# BBoard-JX1.net
KiCad netlist of a schematic drawn in Altium Designer
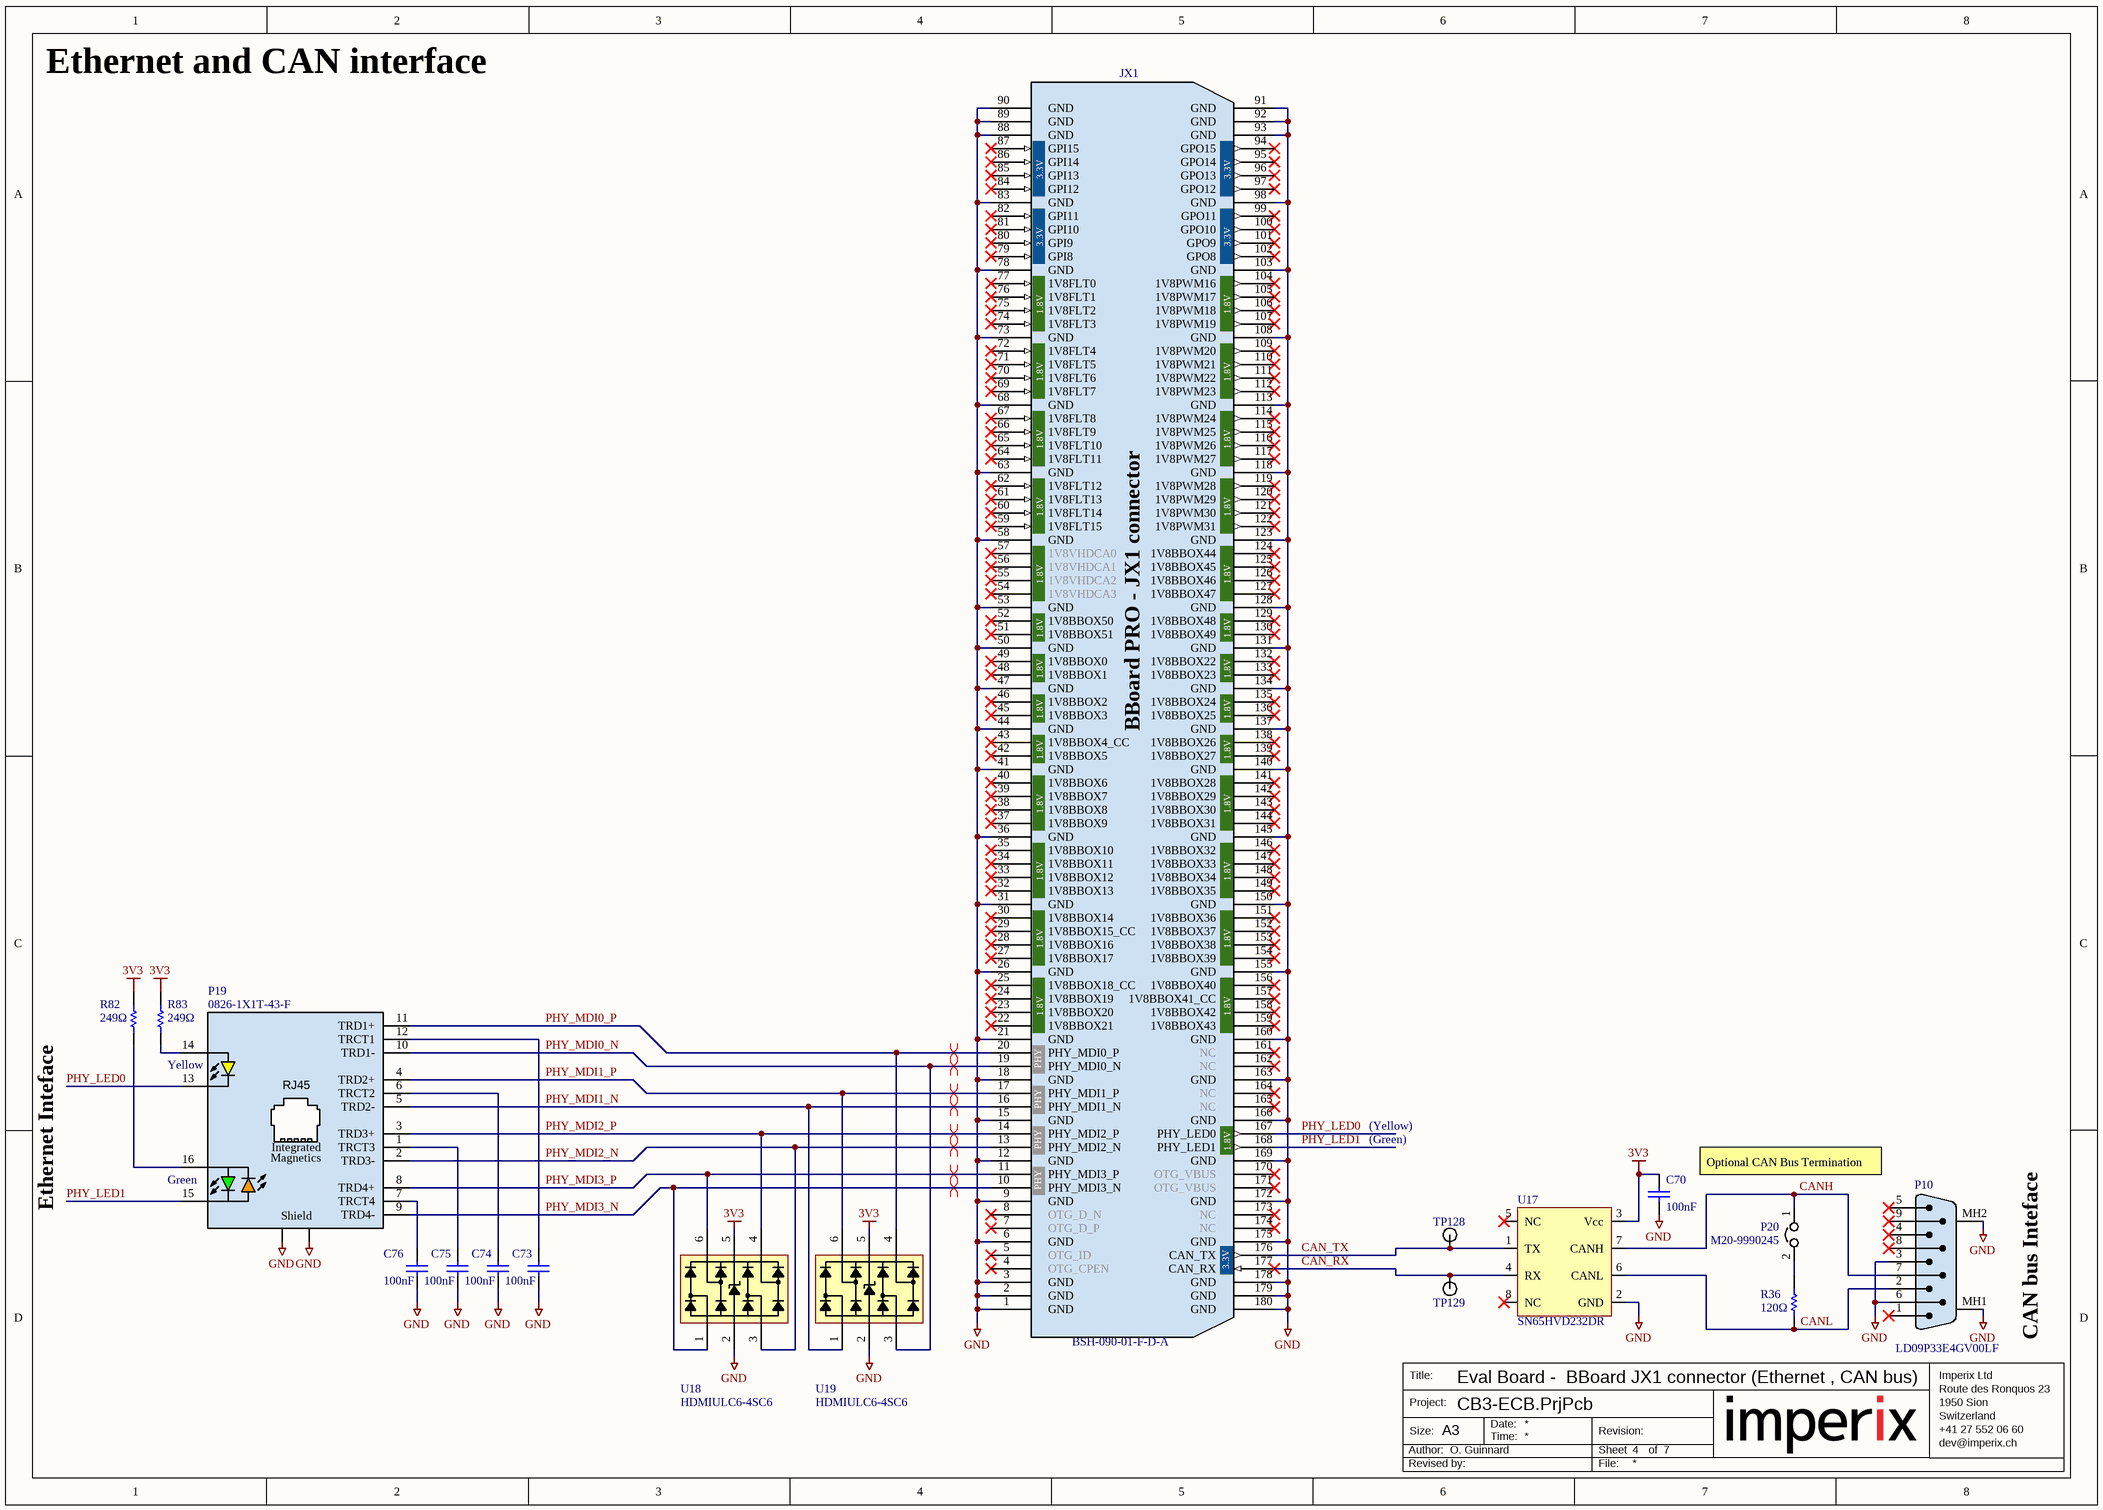
[diagram p0: BBoard-JX1.SchDoc]

(export (version "E")
  (design (tool "Eeschema 10.0.6"))
  (components
    (comp (ref "C70")
      (value "100nF")
      (footprint "CAPC1005L(0402)")
      (description "CAP CER 100NF 25V X7R 0402 10% (Generic Imperix Component)")
      (fields (field (name "TOLERANCE") "10%") (field (name "Comment") "CAP-100NF-25V-X7R-0402-10%"))
      (libsource (lib "CB3-ECB") (part "Capacitor non-polarized"))
    )
    (comp (ref "C73")
      (value "100nF")
      (footprint "CAPC1005L(0402)")
      (description "CAP CER 100NF 25V X7R 0402 10% (Generic Imperix Component)")
      (fields (field (name "TOLERANCE") "10%") (field (name "Comment") "CAP-100NF-25V-X7R-0402-10%"))
      (libsource (lib "CB3-ECB") (part "Capacitor non-polarized"))
    )
    (comp (ref "C74")
      (value "100nF")
      (footprint "CAPC1005L(0402)")
      (description "CAP CER 100NF 25V X7R 0402 10% (Generic Imperix Component)")
      (fields (field (name "TOLERANCE") "10%") (field (name "Comment") "CAP-100NF-25V-X7R-0402-10%"))
      (libsource (lib "CB3-ECB") (part "Capacitor non-polarized"))
    )
    (comp (ref "C75")
      (value "100nF")
      (footprint "CAPC1005L(0402)")
      (description "CAP CER 100NF 25V X7R 0402 10% (Generic Imperix Component)")
      (fields (field (name "TOLERANCE") "10%") (field (name "Comment") "CAP-100NF-25V-X7R-0402-10%"))
      (libsource (lib "CB3-ECB") (part "Capacitor non-polarized"))
    )
    (comp (ref "C76")
      (value "100nF")
      (footprint "CAPC1005L(0402)")
      (description "CAP CER 100NF 25V X7R 0402 10% (Generic Imperix Component)")
      (fields (field (name "TOLERANCE") "10%") (field (name "Comment") "CAP-100NF-25V-X7R-0402-10%"))
      (libsource (lib "CB3-ECB") (part "Capacitor non-polarized"))
    )
    (comp (ref "JX1")
      (value "BSH-090-01-F-D-A")
      (footprint "BSH-090-01-F-D-A")
      (description "JX1 for BBoard")
      (libsource (lib "CB3-ECB") (part "JX1 for Bboard"))
    )
    (comp (ref "P10")
      (value "LD09P33E4GV00LF")
      (footprint "LD09P33E4GV00LF")
      (description "Conn D-Subminiature PIN 9 POS 2.74mm Solder RA Thru-Hole 9 Terminal 1 Port")
      (libsource (lib "CB3-ECB") (part "LD09P33E4GV00LF"))
    )
    (comp (ref "P19")
      (value "0826-1X1T-43-F")
      (footprint "BEL_0826-1X1T-43-F")
      (description "Conn Modular Jack RCP 12 POS 2.03mm Solder RA Thru-Hole 16 Terminal 1 Port Tray")
      (libsource (lib "CB3-ECB") (part "0826-1X1T-43-F"))
    )
    (comp (ref "P20")
      (value "M20-9990245")
      (footprint "M20-9990245")
      (description "Connector Header Through Hole 2 position 0.100\" (2.54mm)")
      (fields (field (name "VOLTAGE") "50V"))
      (libsource (lib "CB3-ECB") (part "Jumper 2-P"))
    )
    (comp (ref "R36")
      (value "120Ω")
      (footprint "RESC1608L(0603)")
      (description "RES SMD 120Ω 1/8W 50PPM 0603 1% (Generic Imperix Component)")
      (fields (field (name "TOLERANCE") "1%") (field (name "Comment") "RES-120Ω-1/8W-50PPM-0603-1%"))
      (libsource (lib "CB3-ECB") (part "Resistor"))
    )
    (comp (ref "R82")
      (value "249Ω")
      (footprint "RESC1005L(0402)")
      (description "RES SMD 249Ω 1/16W 100PPM 0402 1% (Generic Imperix Component)")
      (fields (field (name "TOLERANCE") "1%") (field (name "Comment") "RES-249Ω-1/16W-100PPM-0402-1%"))
      (libsource (lib "CB3-ECB") (part "Resistor"))
    )
    (comp (ref "R83")
      (value "249Ω")
      (footprint "RESC1005L(0402)")
      (description "RES SMD 249Ω 1/16W 100PPM 0402 1% (Generic Imperix Component)")
      (fields (field (name "TOLERANCE") "1%") (field (name "Comment") "RES-249Ω-1/16W-100PPM-0402-1%"))
      (libsource (lib "CB3-ECB") (part "Resistor"))
    )
    (comp (ref "TP128")
      (value "5001")
      (footprint "5001")
      (description "Black PC Test Point, Miniature Phosphor Bronze Silver Plating Through Hole Mounting Type")
      (libsource (lib "CB3-ECB") (part "Testpoint"))
    )
    (comp (ref "TP129")
      (value "5001")
      (footprint "5001")
      (description "Black PC Test Point, Miniature Phosphor Bronze Silver Plating Through Hole Mounting Type")
      (libsource (lib "CB3-ECB") (part "Testpoint"))
    )
    (comp (ref "U17")
      (value "SN65HVD232DR")
      (footprint "SOIC127P600-8AL")
      (description "Texas Instruments - SN65HVD232DR - Can Transceiver, 1MBPS, 1/1, 3.3V, SOIC-8, Full Reel")
      (libsource (lib "CB3-ECB") (part "SN65HVD232DR"))
    )
    (comp (ref "U18")
      (value "HDMIULC6-4SC6")
      (footprint "SOT23-6N")
      (description "HDMIULC6 Series 4 Channel 6 V Bi-Directional ESD Protection - SOT-23-6")
      (libsource (lib "CB3-ECB") (part "HDMIULC6-4SC6"))
    )
    (comp (ref "U19")
      (value "HDMIULC6-4SC6")
      (footprint "SOT23-6N")
      (description "HDMIULC6 Series 4 Channel 6 V Bi-Directional ESD Protection - SOT-23-6")
      (libsource (lib "CB3-ECB") (part "HDMIULC6-4SC6"))
    )
  )
  (nets
    (net (code "1") (name "/CANH") (class "Default")
      (node (ref "P10") (pin "7") (pinfunction "7_7") (pintype "passive"))
      (node (ref "P20") (pin "1") (pinfunction "1_1") (pintype "passive"))
      (node (ref "U17") (pin "7") (pinfunction "CANH_7") (pintype "passive"))
    )
    (net (code "2") (name "/CANL") (class "Default")
      (node (ref "P10") (pin "2") (pinfunction "2_2") (pintype "passive"))
      (node (ref "R36") (pin "1") (pinfunction "1_1") (pintype "passive"))
      (node (ref "U17") (pin "6") (pinfunction "CANL_6") (pintype "passive"))
    )
    (net (code "3") (name "/CAN_RX") (class "Default")
      (node (ref "JX1") (pin "177") (pinfunction "CAN_RX_177") (pintype "input"))
      (node (ref "TP129") (pin "1") (pinfunction "TP_1") (pintype "passive"))
      (node (ref "U17") (pin "4") (pinfunction "RX_4") (pintype "passive"))
    )
    (net (code "4") (name "/CAN_TX") (class "Default")
      (node (ref "JX1") (pin "176") (pinfunction "CAN_TX_176") (pintype "output"))
      (node (ref "TP128") (pin "1") (pinfunction "TP_1") (pintype "passive"))
      (node (ref "U17") (pin "1") (pinfunction "TX_1") (pintype "passive"))
    )
    (net (code "5") (name "/PHY_LED0") (class "Default")
      (node (ref "JX1") (pin "167") (pinfunction "PHY_LED0_167") (pintype "output"))
      (node (ref "P19") (pin "13") (pinfunction "13_13") (pintype "passive"))
    )
    (net (code "6") (name "/PHY_LED1") (class "Default")
      (node (ref "JX1") (pin "168") (pinfunction "PHY_LED1_168") (pintype "output"))
      (node (ref "P19") (pin "15") (pinfunction "15_15") (pintype "passive"))
    )
    (net (code "7") (name "/PHY_MDI0_N") (class "Default")
      (node (ref "JX1") (pin "19") (pinfunction "PHY_MDI0_N_19") (pintype "passive"))
      (node (ref "P19") (pin "10") (pinfunction "TRD1-_10") (pintype "passive"))
      (node (ref "U19") (pin "3") (pinfunction "3_3") (pintype "passive"))
    )
    (net (code "8") (name "/PHY_MDI0_P") (class "Default")
      (node (ref "JX1") (pin "20") (pinfunction "PHY_MDI0_P_20") (pintype "passive"))
      (node (ref "P19") (pin "11") (pinfunction "TRD1+_11") (pintype "passive"))
      (node (ref "U19") (pin "4") (pinfunction "4_4") (pintype "passive"))
    )
    (net (code "9") (name "/PHY_MDI1_N") (class "Default")
      (node (ref "JX1") (pin "16") (pinfunction "PHY_MDI1_N_16") (pintype "passive"))
      (node (ref "P19") (pin "5") (pinfunction "TRD2-_5") (pintype "passive"))
      (node (ref "U19") (pin "1") (pinfunction "1_1") (pintype "passive"))
    )
    (net (code "10") (name "/PHY_MDI1_P") (class "Default")
      (node (ref "JX1") (pin "17") (pinfunction "PHY_MDI1_P_17") (pintype "passive"))
      (node (ref "P19") (pin "4") (pinfunction "TRD2+_4") (pintype "passive"))
      (node (ref "U19") (pin "6") (pinfunction "6_6") (pintype "passive"))
    )
    (net (code "11") (name "/PHY_MDI2_N") (class "Default")
      (node (ref "JX1") (pin "13") (pinfunction "PHY_MDI2_N_13") (pintype "passive"))
      (node (ref "P19") (pin "2") (pinfunction "TRD3-_2") (pintype "passive"))
      (node (ref "U18") (pin "3") (pinfunction "3_3") (pintype "passive"))
    )
    (net (code "12") (name "/PHY_MDI2_P") (class "Default")
      (node (ref "JX1") (pin "14") (pinfunction "PHY_MDI2_P_14") (pintype "passive"))
      (node (ref "P19") (pin "3") (pinfunction "TRD3+_3") (pintype "passive"))
      (node (ref "U18") (pin "4") (pinfunction "4_4") (pintype "passive"))
    )
    (net (code "13") (name "/PHY_MDI3_N") (class "Default")
      (node (ref "JX1") (pin "10") (pinfunction "PHY_MDI3_N_10") (pintype "passive"))
      (node (ref "P19") (pin "9") (pinfunction "TRD4-_9") (pintype "passive"))
      (node (ref "U18") (pin "1") (pinfunction "1_1") (pintype "passive"))
    )
    (net (code "14") (name "/PHY_MDI3_P") (class "Default")
      (node (ref "JX1") (pin "11") (pinfunction "PHY_MDI3_P_11") (pintype "passive"))
      (node (ref "P19") (pin "8") (pinfunction "TRD4+_8") (pintype "passive"))
      (node (ref "U18") (pin "6") (pinfunction "6_6") (pintype "passive"))
    )
    (net (code "15") (name "3V3") (class "Default")
      (node (ref "C70") (pin "2") (pinfunction "2_2") (pintype "passive"))
      (node (ref "R82") (pin "2") (pinfunction "2_2") (pintype "passive"))
      (node (ref "R83") (pin "2") (pinfunction "2_2") (pintype "passive"))
      (node (ref "U17") (pin "3") (pinfunction "Vcc_3") (pintype "passive"))
      (node (ref "U18") (pin "5") (pinfunction "5_5") (pintype "passive"))
      (node (ref "U19") (pin "5") (pinfunction "5_5") (pintype "passive"))
    )
    (net (code "16") (name "GND") (class "Default")
      (node (ref "C70") (pin "1") (pinfunction "1_1") (pintype "passive"))
      (node (ref "C73") (pin "1") (pinfunction "1_1") (pintype "passive"))
      (node (ref "C74") (pin "1") (pinfunction "1_1") (pintype "passive"))
      (node (ref "C75") (pin "1") (pinfunction "1_1") (pintype "passive"))
      (node (ref "C76") (pin "1") (pinfunction "1_1") (pintype "passive"))
      (node (ref "JX1") (pin "1") (pinfunction "GND_1") (pintype "power_in"))
      (node (ref "JX1") (pin "103") (pinfunction "GND_103") (pintype "power_in"))
      (node (ref "JX1") (pin "108") (pinfunction "GND_108") (pintype "power_in"))
      (node (ref "JX1") (pin "113") (pinfunction "GND_113") (pintype "power_in"))
      (node (ref "JX1") (pin "118") (pinfunction "GND_118") (pintype "power_in"))
      (node (ref "JX1") (pin "12") (pinfunction "GND_12") (pintype "power_in"))
      (node (ref "JX1") (pin "123") (pinfunction "GND_123") (pintype "power_in"))
      (node (ref "JX1") (pin "128") (pinfunction "GND_128") (pintype "power_in"))
      (node (ref "JX1") (pin "131") (pinfunction "GND_131") (pintype "power_in"))
      (node (ref "JX1") (pin "134") (pinfunction "GND_134") (pintype "power_in"))
      (node (ref "JX1") (pin "137") (pinfunction "GND_137") (pintype "power_in"))
      (node (ref "JX1") (pin "140") (pinfunction "GND_140") (pintype "power_in"))
      (node (ref "JX1") (pin "145") (pinfunction "GND_145") (pintype "power_in"))
      (node (ref "JX1") (pin "15") (pinfunction "GND_15") (pintype "power_in"))
      (node (ref "JX1") (pin "150") (pinfunction "GND_150") (pintype "power_in"))
      (node (ref "JX1") (pin "155") (pinfunction "GND_155") (pintype "power_in"))
      (node (ref "JX1") (pin "160") (pinfunction "GND_160") (pintype "power_in"))
      (node (ref "JX1") (pin "163") (pinfunction "GND_163") (pintype "power_in"))
      (node (ref "JX1") (pin "166") (pinfunction "GND_166") (pintype "power_in"))
      (node (ref "JX1") (pin "169") (pinfunction "GND_169") (pintype "power_in"))
      (node (ref "JX1") (pin "172") (pinfunction "GND_172") (pintype "power_in"))
      (node (ref "JX1") (pin "175") (pinfunction "GND_175") (pintype "power_in"))
      (node (ref "JX1") (pin "178") (pinfunction "GND_178") (pintype "power_in"))
      (node (ref "JX1") (pin "179") (pinfunction "GND_179") (pintype "power_in"))
      (node (ref "JX1") (pin "18") (pinfunction "GND_18") (pintype "power_in"))
      (node (ref "JX1") (pin "180") (pinfunction "GND_180") (pintype "power_in"))
      (node (ref "JX1") (pin "2") (pinfunction "GND_2") (pintype "power_in"))
      (node (ref "JX1") (pin "21") (pinfunction "GND_21") (pintype "power_in"))
      (node (ref "JX1") (pin "26") (pinfunction "GND_26") (pintype "power_in"))
      (node (ref "JX1") (pin "3") (pinfunction "GND_3") (pintype "power_in"))
      (node (ref "JX1") (pin "31") (pinfunction "GND_31") (pintype "power_in"))
      (node (ref "JX1") (pin "36") (pinfunction "GND_36") (pintype "power_in"))
      (node (ref "JX1") (pin "41") (pinfunction "GND_41") (pintype "power_in"))
      (node (ref "JX1") (pin "44") (pinfunction "GND_44") (pintype "power_in"))
      (node (ref "JX1") (pin "47") (pinfunction "GND_47") (pintype "power_in"))
      (node (ref "JX1") (pin "50") (pinfunction "GND_50") (pintype "power_in"))
      (node (ref "JX1") (pin "53") (pinfunction "GND_53") (pintype "power_in"))
      (node (ref "JX1") (pin "58") (pinfunction "GND_58") (pintype "power_in"))
      (node (ref "JX1") (pin "6") (pinfunction "GND_6") (pintype "power_in"))
      (node (ref "JX1") (pin "63") (pinfunction "GND_63") (pintype "power_in"))
      (node (ref "JX1") (pin "68") (pinfunction "GND_68") (pintype "power_in"))
      (node (ref "JX1") (pin "73") (pinfunction "GND_73") (pintype "power_in"))
      (node (ref "JX1") (pin "78") (pinfunction "GND_78") (pintype "power_in"))
      (node (ref "JX1") (pin "83") (pinfunction "GND_83") (pintype "power_in"))
      (node (ref "JX1") (pin "88") (pinfunction "GND_88") (pintype "power_in"))
      (node (ref "JX1") (pin "89") (pinfunction "GND_89") (pintype "power_in"))
      (node (ref "JX1") (pin "9") (pinfunction "GND_9") (pintype "power_in"))
      (node (ref "JX1") (pin "90") (pinfunction "GND_90") (pintype "power_in"))
      (node (ref "JX1") (pin "91") (pinfunction "GND_91") (pintype "power_in"))
      (node (ref "JX1") (pin "92") (pinfunction "GND_92") (pintype "power_in"))
      (node (ref "JX1") (pin "93") (pinfunction "GND_93") (pintype "power_in"))
      (node (ref "JX1") (pin "98") (pinfunction "GND_98") (pintype "power_in"))
      (node (ref "P10") (pin "3") (pinfunction "3_3") (pintype "passive"))
      (node (ref "P10") (pin "6") (pinfunction "6_6") (pintype "passive"))
      (node (ref "P10") (pin "MH1") (pinfunction "SH_MH1") (pintype "passive"))
      (node (ref "P10") (pin "MH2") (pinfunction "SH_MH2") (pintype "passive"))
      (node (ref "P19") (pin "S1") (pinfunction "SHIELD_S1") (pintype "passive"))
      (node (ref "P19") (pin "S2") (pinfunction "SHIELD_S2") (pintype "passive"))
      (node (ref "U17") (pin "2") (pinfunction "GND_2") (pintype "passive"))
      (node (ref "U18") (pin "2") (pinfunction "2_2") (pintype "passive"))
      (node (ref "U19") (pin "2") (pinfunction "2_2") (pintype "passive"))
    )
    (net (code "17") (name "Net-(P19-Pad14)") (class "Default")
      (node (ref "P19") (pin "14") (pinfunction "14_14") (pintype "passive"))
      (node (ref "R83") (pin "1") (pinfunction "1_1") (pintype "passive"))
    )
    (net (code "18") (name "Net-(P19-Pad16)") (class "Default")
      (node (ref "P19") (pin "16") (pinfunction "16_16") (pintype "passive"))
      (node (ref "R82") (pin "1") (pinfunction "1_1") (pintype "passive"))
    )
    (net (code "19") (name "Net-(P19-TRCT1)") (class "Default")
      (node (ref "C73") (pin "2") (pinfunction "2_2") (pintype "passive"))
      (node (ref "P19") (pin "12") (pinfunction "TRCT1_12") (pintype "passive"))
    )
    (net (code "20") (name "Net-(P19-TRCT2)") (class "Default")
      (node (ref "C74") (pin "2") (pinfunction "2_2") (pintype "passive"))
      (node (ref "P19") (pin "6") (pinfunction "TRCT2_6") (pintype "passive"))
    )
    (net (code "21") (name "Net-(P19-TRCT3)") (class "Default")
      (node (ref "C75") (pin "2") (pinfunction "2_2") (pintype "passive"))
      (node (ref "P19") (pin "1") (pinfunction "TRCT3_1") (pintype "passive"))
    )
    (net (code "22") (name "Net-(P19-TRCT4)") (class "Default")
      (node (ref "C76") (pin "2") (pinfunction "2_2") (pintype "passive"))
      (node (ref "P19") (pin "7") (pinfunction "TRCT4_7") (pintype "passive"))
    )
    (net (code "23") (name "Net-(P20-Pad2)") (class "Default")
      (node (ref "P20") (pin "2") (pinfunction "2_2") (pintype "passive"))
      (node (ref "R36") (pin "2") (pinfunction "2_2") (pintype "passive"))
    )
    (net (code "24") (name "unconnected-(JX1-1V8BBOX0-Pad49)") (class "Default")
      (node (ref "JX1") (pin "49") (pinfunction "1V8BBOX0_49") (pintype "passive+no_connect"))
    )
    (net (code "25") (name "unconnected-(JX1-1V8BBOX1-Pad48)") (class "Default")
      (node (ref "JX1") (pin "48") (pinfunction "1V8BBOX1_48") (pintype "passive+no_connect"))
    )
    (net (code "26") (name "unconnected-(JX1-1V8BBOX2-Pad46)") (class "Default")
      (node (ref "JX1") (pin "46") (pinfunction "1V8BBOX2_46") (pintype "passive+no_connect"))
    )
    (net (code "27") (name "unconnected-(JX1-1V8BBOX3-Pad45)") (class "Default")
      (node (ref "JX1") (pin "45") (pinfunction "1V8BBOX3_45") (pintype "passive+no_connect"))
    )
    (net (code "28") (name "unconnected-(JX1-1V8BBOX4_CC-Pad43)") (class "Default")
      (node (ref "JX1") (pin "43") (pinfunction "1V8BBOX4_CC_43") (pintype "passive+no_connect"))
    )
    (net (code "29") (name "unconnected-(JX1-1V8BBOX5-Pad42)") (class "Default")
      (node (ref "JX1") (pin "42") (pinfunction "1V8BBOX5_42") (pintype "passive+no_connect"))
    )
    (net (code "30") (name "unconnected-(JX1-1V8BBOX6-Pad40)") (class "Default")
      (node (ref "JX1") (pin "40") (pinfunction "1V8BBOX6_40") (pintype "passive+no_connect"))
    )
    (net (code "31") (name "unconnected-(JX1-1V8BBOX7-Pad39)") (class "Default")
      (node (ref "JX1") (pin "39") (pinfunction "1V8BBOX7_39") (pintype "passive+no_connect"))
    )
    (net (code "32") (name "unconnected-(JX1-1V8BBOX8-Pad38)") (class "Default")
      (node (ref "JX1") (pin "38") (pinfunction "1V8BBOX8_38") (pintype "passive+no_connect"))
    )
    (net (code "33") (name "unconnected-(JX1-1V8BBOX9-Pad37)") (class "Default")
      (node (ref "JX1") (pin "37") (pinfunction "1V8BBOX9_37") (pintype "passive+no_connect"))
    )
    (net (code "34") (name "unconnected-(JX1-1V8BBOX10-Pad35)") (class "Default")
      (node (ref "JX1") (pin "35") (pinfunction "1V8BBOX10_35") (pintype "passive+no_connect"))
    )
    (net (code "35") (name "unconnected-(JX1-1V8BBOX11-Pad34)") (class "Default")
      (node (ref "JX1") (pin "34") (pinfunction "1V8BBOX11_34") (pintype "passive+no_connect"))
    )
    (net (code "36") (name "unconnected-(JX1-1V8BBOX12-Pad33)") (class "Default")
      (node (ref "JX1") (pin "33") (pinfunction "1V8BBOX12_33") (pintype "passive+no_connect"))
    )
    (net (code "37") (name "unconnected-(JX1-1V8BBOX13-Pad32)") (class "Default")
      (node (ref "JX1") (pin "32") (pinfunction "1V8BBOX13_32") (pintype "passive+no_connect"))
    )
    (net (code "38") (name "unconnected-(JX1-1V8BBOX14-Pad30)") (class "Default")
      (node (ref "JX1") (pin "30") (pinfunction "1V8BBOX14_30") (pintype "passive+no_connect"))
    )
    (net (code "39") (name "unconnected-(JX1-1V8BBOX15_CC-Pad29)") (class "Default")
      (node (ref "JX1") (pin "29") (pinfunction "1V8BBOX15_CC_29") (pintype "passive+no_connect"))
    )
    (net (code "40") (name "unconnected-(JX1-1V8BBOX16-Pad28)") (class "Default")
      (node (ref "JX1") (pin "28") (pinfunction "1V8BBOX16_28") (pintype "passive+no_connect"))
    )
    (net (code "41") (name "unconnected-(JX1-1V8BBOX17-Pad27)") (class "Default")
      (node (ref "JX1") (pin "27") (pinfunction "1V8BBOX17_27") (pintype "passive+no_connect"))
    )
    (net (code "42") (name "unconnected-(JX1-1V8BBOX18_CC-Pad25)") (class "Default")
      (node (ref "JX1") (pin "25") (pinfunction "1V8BBOX18_CC_25") (pintype "passive+no_connect"))
    )
    (net (code "43") (name "unconnected-(JX1-1V8BBOX19-Pad24)") (class "Default")
      (node (ref "JX1") (pin "24") (pinfunction "1V8BBOX19_24") (pintype "passive+no_connect"))
    )
    (net (code "44") (name "unconnected-(JX1-1V8BBOX20-Pad23)") (class "Default")
      (node (ref "JX1") (pin "23") (pinfunction "1V8BBOX20_23") (pintype "passive+no_connect"))
    )
    (net (code "45") (name "unconnected-(JX1-1V8BBOX21-Pad22)") (class "Default")
      (node (ref "JX1") (pin "22") (pinfunction "1V8BBOX21_22") (pintype "passive+no_connect"))
    )
    (net (code "46") (name "unconnected-(JX1-1V8BBOX22-Pad132)") (class "Default")
      (node (ref "JX1") (pin "132") (pinfunction "1V8BBOX22_132") (pintype "passive+no_connect"))
    )
    (net (code "47") (name "unconnected-(JX1-1V8BBOX23-Pad133)") (class "Default")
      (node (ref "JX1") (pin "133") (pinfunction "1V8BBOX23_133") (pintype "passive+no_connect"))
    )
    (net (code "48") (name "unconnected-(JX1-1V8BBOX24-Pad135)") (class "Default")
      (node (ref "JX1") (pin "135") (pinfunction "1V8BBOX24_135") (pintype "passive+no_connect"))
    )
    (net (code "49") (name "unconnected-(JX1-1V8BBOX25-Pad136)") (class "Default")
      (node (ref "JX1") (pin "136") (pinfunction "1V8BBOX25_136") (pintype "passive+no_connect"))
    )
    (net (code "50") (name "unconnected-(JX1-1V8BBOX26-Pad138)") (class "Default")
      (node (ref "JX1") (pin "138") (pinfunction "1V8BBOX26_138") (pintype "passive+no_connect"))
    )
    (net (code "51") (name "unconnected-(JX1-1V8BBOX27-Pad139)") (class "Default")
      (node (ref "JX1") (pin "139") (pinfunction "1V8BBOX27_139") (pintype "passive+no_connect"))
    )
    (net (code "52") (name "unconnected-(JX1-1V8BBOX28-Pad141)") (class "Default")
      (node (ref "JX1") (pin "141") (pinfunction "1V8BBOX28_141") (pintype "passive+no_connect"))
    )
    (net (code "53") (name "unconnected-(JX1-1V8BBOX29-Pad142)") (class "Default")
      (node (ref "JX1") (pin "142") (pinfunction "1V8BBOX29_142") (pintype "passive+no_connect"))
    )
    (net (code "54") (name "unconnected-(JX1-1V8BBOX30-Pad143)") (class "Default")
      (node (ref "JX1") (pin "143") (pinfunction "1V8BBOX30_143") (pintype "passive+no_connect"))
    )
    (net (code "55") (name "unconnected-(JX1-1V8BBOX31-Pad144)") (class "Default")
      (node (ref "JX1") (pin "144") (pinfunction "1V8BBOX31_144") (pintype "passive+no_connect"))
    )
    (net (code "56") (name "unconnected-(JX1-1V8BBOX32-Pad146)") (class "Default")
      (node (ref "JX1") (pin "146") (pinfunction "1V8BBOX32_146") (pintype "passive+no_connect"))
    )
    (net (code "57") (name "unconnected-(JX1-1V8BBOX33-Pad147)") (class "Default")
      (node (ref "JX1") (pin "147") (pinfunction "1V8BBOX33_147") (pintype "passive+no_connect"))
    )
    (net (code "58") (name "unconnected-(JX1-1V8BBOX34-Pad148)") (class "Default")
      (node (ref "JX1") (pin "148") (pinfunction "1V8BBOX34_148") (pintype "passive+no_connect"))
    )
    (net (code "59") (name "unconnected-(JX1-1V8BBOX35-Pad149)") (class "Default")
      (node (ref "JX1") (pin "149") (pinfunction "1V8BBOX35_149") (pintype "passive+no_connect"))
    )
    (net (code "60") (name "unconnected-(JX1-1V8BBOX36-Pad151)") (class "Default")
      (node (ref "JX1") (pin "151") (pinfunction "1V8BBOX36_151") (pintype "passive+no_connect"))
    )
    (net (code "61") (name "unconnected-(JX1-1V8BBOX37-Pad152)") (class "Default")
      (node (ref "JX1") (pin "152") (pinfunction "1V8BBOX37_152") (pintype "passive+no_connect"))
    )
    (net (code "62") (name "unconnected-(JX1-1V8BBOX38-Pad153)") (class "Default")
      (node (ref "JX1") (pin "153") (pinfunction "1V8BBOX38_153") (pintype "passive+no_connect"))
    )
    (net (code "63") (name "unconnected-(JX1-1V8BBOX39-Pad154)") (class "Default")
      (node (ref "JX1") (pin "154") (pinfunction "1V8BBOX39_154") (pintype "passive+no_connect"))
    )
    (net (code "64") (name "unconnected-(JX1-1V8BBOX40-Pad156)") (class "Default")
      (node (ref "JX1") (pin "156") (pinfunction "1V8BBOX40_156") (pintype "passive+no_connect"))
    )
    (net (code "65") (name "unconnected-(JX1-1V8BBOX41_CC-Pad157)") (class "Default")
      (node (ref "JX1") (pin "157") (pinfunction "1V8BBOX41_CC_157") (pintype "passive+no_connect"))
    )
    (net (code "66") (name "unconnected-(JX1-1V8BBOX42-Pad158)") (class "Default")
      (node (ref "JX1") (pin "158") (pinfunction "1V8BBOX42_158") (pintype "passive+no_connect"))
    )
    (net (code "67") (name "unconnected-(JX1-1V8BBOX43-Pad159)") (class "Default")
      (node (ref "JX1") (pin "159") (pinfunction "1V8BBOX43_159") (pintype "passive+no_connect"))
    )
    (net (code "68") (name "unconnected-(JX1-1V8BBOX44-Pad124)") (class "Default")
      (node (ref "JX1") (pin "124") (pinfunction "1V8BBOX44_124") (pintype "passive+no_connect"))
    )
    (net (code "69") (name "unconnected-(JX1-1V8BBOX45-Pad125)") (class "Default")
      (node (ref "JX1") (pin "125") (pinfunction "1V8BBOX45_125") (pintype "passive+no_connect"))
    )
    (net (code "70") (name "unconnected-(JX1-1V8BBOX46-Pad126)") (class "Default")
      (node (ref "JX1") (pin "126") (pinfunction "1V8BBOX46_126") (pintype "passive+no_connect"))
    )
    (net (code "71") (name "unconnected-(JX1-1V8BBOX47-Pad127)") (class "Default")
      (node (ref "JX1") (pin "127") (pinfunction "1V8BBOX47_127") (pintype "passive+no_connect"))
    )
    (net (code "72") (name "unconnected-(JX1-1V8BBOX48-Pad129)") (class "Default")
      (node (ref "JX1") (pin "129") (pinfunction "1V8BBOX48_129") (pintype "passive+no_connect"))
    )
    (net (code "73") (name "unconnected-(JX1-1V8BBOX49-Pad130)") (class "Default")
      (node (ref "JX1") (pin "130") (pinfunction "1V8BBOX49_130") (pintype "passive+no_connect"))
    )
    (net (code "74") (name "unconnected-(JX1-1V8BBOX50-Pad52)") (class "Default")
      (node (ref "JX1") (pin "52") (pinfunction "1V8BBOX50_52") (pintype "passive+no_connect"))
    )
    (net (code "75") (name "unconnected-(JX1-1V8BBOX51-Pad51)") (class "Default")
      (node (ref "JX1") (pin "51") (pinfunction "1V8BBOX51_51") (pintype "passive+no_connect"))
    )
    (net (code "76") (name "unconnected-(JX1-1V8FLT0-Pad77)") (class "Default")
      (node (ref "JX1") (pin "77") (pinfunction "1V8FLT0_77") (pintype "input+no_connect"))
    )
    (net (code "77") (name "unconnected-(JX1-1V8FLT1-Pad76)") (class "Default")
      (node (ref "JX1") (pin "76") (pinfunction "1V8FLT1_76") (pintype "input+no_connect"))
    )
    (net (code "78") (name "unconnected-(JX1-1V8FLT2-Pad75)") (class "Default")
      (node (ref "JX1") (pin "75") (pinfunction "1V8FLT2_75") (pintype "input+no_connect"))
    )
    (net (code "79") (name "unconnected-(JX1-1V8FLT3-Pad74)") (class "Default")
      (node (ref "JX1") (pin "74") (pinfunction "1V8FLT3_74") (pintype "input+no_connect"))
    )
    (net (code "80") (name "unconnected-(JX1-1V8FLT4-Pad72)") (class "Default")
      (node (ref "JX1") (pin "72") (pinfunction "1V8FLT4_72") (pintype "input+no_connect"))
    )
    (net (code "81") (name "unconnected-(JX1-1V8FLT5-Pad71)") (class "Default")
      (node (ref "JX1") (pin "71") (pinfunction "1V8FLT5_71") (pintype "input+no_connect"))
    )
    (net (code "82") (name "unconnected-(JX1-1V8FLT6-Pad70)") (class "Default")
      (node (ref "JX1") (pin "70") (pinfunction "1V8FLT6_70") (pintype "input+no_connect"))
    )
    (net (code "83") (name "unconnected-(JX1-1V8FLT7-Pad69)") (class "Default")
      (node (ref "JX1") (pin "69") (pinfunction "1V8FLT7_69") (pintype "input+no_connect"))
    )
    (net (code "84") (name "unconnected-(JX1-1V8FLT8-Pad67)") (class "Default")
      (node (ref "JX1") (pin "67") (pinfunction "1V8FLT8_67") (pintype "input+no_connect"))
    )
    (net (code "85") (name "unconnected-(JX1-1V8FLT9-Pad66)") (class "Default")
      (node (ref "JX1") (pin "66") (pinfunction "1V8FLT9_66") (pintype "input+no_connect"))
    )
    (net (code "86") (name "unconnected-(JX1-1V8FLT10-Pad65)") (class "Default")
      (node (ref "JX1") (pin "65") (pinfunction "1V8FLT10_65") (pintype "input+no_connect"))
    )
    (net (code "87") (name "unconnected-(JX1-1V8FLT11-Pad64)") (class "Default")
      (node (ref "JX1") (pin "64") (pinfunction "1V8FLT11_64") (pintype "input+no_connect"))
    )
    (net (code "88") (name "unconnected-(JX1-1V8FLT12-Pad62)") (class "Default")
      (node (ref "JX1") (pin "62") (pinfunction "1V8FLT12_62") (pintype "input+no_connect"))
    )
    (net (code "89") (name "unconnected-(JX1-1V8FLT13-Pad61)") (class "Default")
      (node (ref "JX1") (pin "61") (pinfunction "1V8FLT13_61") (pintype "input+no_connect"))
    )
    (net (code "90") (name "unconnected-(JX1-1V8FLT14-Pad60)") (class "Default")
      (node (ref "JX1") (pin "60") (pinfunction "1V8FLT14_60") (pintype "input+no_connect"))
    )
    (net (code "91") (name "unconnected-(JX1-1V8FLT15-Pad59)") (class "Default")
      (node (ref "JX1") (pin "59") (pinfunction "1V8FLT15_59") (pintype "input+no_connect"))
    )
    (net (code "92") (name "unconnected-(JX1-1V8PWM16-Pad104)") (class "Default")
      (node (ref "JX1") (pin "104") (pinfunction "1V8PWM16_104") (pintype "output+no_connect"))
    )
    (net (code "93") (name "unconnected-(JX1-1V8PWM17-Pad105)") (class "Default")
      (node (ref "JX1") (pin "105") (pinfunction "1V8PWM17_105") (pintype "output+no_connect"))
    )
    (net (code "94") (name "unconnected-(JX1-1V8PWM18-Pad106)") (class "Default")
      (node (ref "JX1") (pin "106") (pinfunction "1V8PWM18_106") (pintype "output+no_connect"))
    )
    (net (code "95") (name "unconnected-(JX1-1V8PWM19-Pad107)") (class "Default")
      (node (ref "JX1") (pin "107") (pinfunction "1V8PWM19_107") (pintype "output+no_connect"))
    )
    (net (code "96") (name "unconnected-(JX1-1V8PWM20-Pad109)") (class "Default")
      (node (ref "JX1") (pin "109") (pinfunction "1V8PWM20_109") (pintype "output+no_connect"))
    )
    (net (code "97") (name "unconnected-(JX1-1V8PWM21-Pad110)") (class "Default")
      (node (ref "JX1") (pin "110") (pinfunction "1V8PWM21_110") (pintype "output+no_connect"))
    )
    (net (code "98") (name "unconnected-(JX1-1V8PWM22-Pad111)") (class "Default")
      (node (ref "JX1") (pin "111") (pinfunction "1V8PWM22_111") (pintype "output+no_connect"))
    )
    (net (code "99") (name "unconnected-(JX1-1V8PWM23-Pad112)") (class "Default")
      (node (ref "JX1") (pin "112") (pinfunction "1V8PWM23_112") (pintype "output+no_connect"))
    )
    (net (code "100") (name "unconnected-(JX1-1V8PWM24-Pad114)") (class "Default")
      (node (ref "JX1") (pin "114") (pinfunction "1V8PWM24_114") (pintype "output+no_connect"))
    )
    (net (code "101") (name "unconnected-(JX1-1V8PWM25-Pad115)") (class "Default")
      (node (ref "JX1") (pin "115") (pinfunction "1V8PWM25_115") (pintype "output+no_connect"))
    )
    (net (code "102") (name "unconnected-(JX1-1V8PWM26-Pad116)") (class "Default")
      (node (ref "JX1") (pin "116") (pinfunction "1V8PWM26_116") (pintype "output+no_connect"))
    )
    (net (code "103") (name "unconnected-(JX1-1V8PWM27-Pad117)") (class "Default")
      (node (ref "JX1") (pin "117") (pinfunction "1V8PWM27_117") (pintype "output+no_connect"))
    )
    (net (code "104") (name "unconnected-(JX1-1V8PWM28-Pad119)") (class "Default")
      (node (ref "JX1") (pin "119") (pinfunction "1V8PWM28_119") (pintype "output+no_connect"))
    )
    (net (code "105") (name "unconnected-(JX1-1V8PWM29-Pad120)") (class "Default")
      (node (ref "JX1") (pin "120") (pinfunction "1V8PWM29_120") (pintype "output+no_connect"))
    )
    (net (code "106") (name "unconnected-(JX1-1V8PWM30-Pad121)") (class "Default")
      (node (ref "JX1") (pin "121") (pinfunction "1V8PWM30_121") (pintype "output+no_connect"))
    )
    (net (code "107") (name "unconnected-(JX1-1V8PWM31-Pad122)") (class "Default")
      (node (ref "JX1") (pin "122") (pinfunction "1V8PWM31_122") (pintype "output+no_connect"))
    )
    (net (code "108") (name "unconnected-(JX1-1V8VHDCA0-Pad57)") (class "Default")
      (node (ref "JX1") (pin "57") (pinfunction "1V8VHDCA0_57") (pintype "passive+no_connect"))
    )
    (net (code "109") (name "unconnected-(JX1-1V8VHDCA1-Pad56)") (class "Default")
      (node (ref "JX1") (pin "56") (pinfunction "1V8VHDCA1_56") (pintype "passive+no_connect"))
    )
    (net (code "110") (name "unconnected-(JX1-1V8VHDCA2-Pad55)") (class "Default")
      (node (ref "JX1") (pin "55") (pinfunction "1V8VHDCA2_55") (pintype "passive+no_connect"))
    )
    (net (code "111") (name "unconnected-(JX1-1V8VHDCA3-Pad54)") (class "Default")
      (node (ref "JX1") (pin "54") (pinfunction "1V8VHDCA3_54") (pintype "passive+no_connect"))
    )
    (net (code "112") (name "unconnected-(JX1-GPI8-Pad79)") (class "Default")
      (node (ref "JX1") (pin "79") (pinfunction "GPI8_79") (pintype "input+no_connect"))
    )
    (net (code "113") (name "unconnected-(JX1-GPI9-Pad80)") (class "Default")
      (node (ref "JX1") (pin "80") (pinfunction "GPI9_80") (pintype "input+no_connect"))
    )
    (net (code "114") (name "unconnected-(JX1-GPI10-Pad81)") (class "Default")
      (node (ref "JX1") (pin "81") (pinfunction "GPI10_81") (pintype "input+no_connect"))
    )
    (net (code "115") (name "unconnected-(JX1-GPI11-Pad82)") (class "Default")
      (node (ref "JX1") (pin "82") (pinfunction "GPI11_82") (pintype "input+no_connect"))
    )
    (net (code "116") (name "unconnected-(JX1-GPI12-Pad84)") (class "Default")
      (node (ref "JX1") (pin "84") (pinfunction "GPI12_84") (pintype "input+no_connect"))
    )
    (net (code "117") (name "unconnected-(JX1-GPI13-Pad85)") (class "Default")
      (node (ref "JX1") (pin "85") (pinfunction "GPI13_85") (pintype "input+no_connect"))
    )
    (net (code "118") (name "unconnected-(JX1-GPI14-Pad86)") (class "Default")
      (node (ref "JX1") (pin "86") (pinfunction "GPI14_86") (pintype "input+no_connect"))
    )
    (net (code "119") (name "unconnected-(JX1-GPI15-Pad87)") (class "Default")
      (node (ref "JX1") (pin "87") (pinfunction "GPI15_87") (pintype "input+no_connect"))
    )
    (net (code "120") (name "unconnected-(JX1-GPO8-Pad102)") (class "Default")
      (node (ref "JX1") (pin "102") (pinfunction "GPO8_102") (pintype "output+no_connect"))
    )
    (net (code "121") (name "unconnected-(JX1-GPO9-Pad101)") (class "Default")
      (node (ref "JX1") (pin "101") (pinfunction "GPO9_101") (pintype "output+no_connect"))
    )
    (net (code "122") (name "unconnected-(JX1-GPO10-Pad100)") (class "Default")
      (node (ref "JX1") (pin "100") (pinfunction "GPO10_100") (pintype "output+no_connect"))
    )
    (net (code "123") (name "unconnected-(JX1-GPO11-Pad99)") (class "Default")
      (node (ref "JX1") (pin "99") (pinfunction "GPO11_99") (pintype "output+no_connect"))
    )
    (net (code "124") (name "unconnected-(JX1-GPO12-Pad97)") (class "Default")
      (node (ref "JX1") (pin "97") (pinfunction "GPO12_97") (pintype "output+no_connect"))
    )
    (net (code "125") (name "unconnected-(JX1-GPO13-Pad96)") (class "Default")
      (node (ref "JX1") (pin "96") (pinfunction "GPO13_96") (pintype "output+no_connect"))
    )
    (net (code "126") (name "unconnected-(JX1-GPO14-Pad95)") (class "Default")
      (node (ref "JX1") (pin "95") (pinfunction "GPO14_95") (pintype "output+no_connect"))
    )
    (net (code "127") (name "unconnected-(JX1-GPO15-Pad94)") (class "Default")
      (node (ref "JX1") (pin "94") (pinfunction "GPO15_94") (pintype "output+no_connect"))
    )
    (net (code "128") (name "unconnected-(JX1-NC-Pad161)") (class "Default")
      (node (ref "JX1") (pin "161") (pinfunction "NC_161") (pintype "passive+no_connect"))
    )
    (net (code "129") (name "unconnected-(JX1-NC-Pad162)") (class "Default")
      (node (ref "JX1") (pin "162") (pinfunction "NC_162") (pintype "passive+no_connect"))
    )
    (net (code "130") (name "unconnected-(JX1-NC-Pad164)") (class "Default")
      (node (ref "JX1") (pin "164") (pinfunction "NC_164") (pintype "passive+no_connect"))
    )
    (net (code "131") (name "unconnected-(JX1-NC-Pad165)") (class "Default")
      (node (ref "JX1") (pin "165") (pinfunction "NC_165") (pintype "passive+no_connect"))
    )
    (net (code "132") (name "unconnected-(JX1-NC-Pad173)") (class "Default")
      (node (ref "JX1") (pin "173") (pinfunction "NC_173") (pintype "passive+no_connect"))
    )
    (net (code "133") (name "unconnected-(JX1-NC-Pad174)") (class "Default")
      (node (ref "JX1") (pin "174") (pinfunction "NC_174") (pintype "passive+no_connect"))
    )
    (net (code "134") (name "unconnected-(JX1-OTG_CPEN-Pad4)") (class "Default")
      (node (ref "JX1") (pin "4") (pinfunction "OTG_CPEN_4") (pintype "passive+no_connect"))
    )
    (net (code "135") (name "unconnected-(JX1-OTG_D_N-Pad8)") (class "Default")
      (node (ref "JX1") (pin "8") (pinfunction "OTG_D_N_8") (pintype "passive+no_connect"))
    )
    (net (code "136") (name "unconnected-(JX1-OTG_D_P-Pad7)") (class "Default")
      (node (ref "JX1") (pin "7") (pinfunction "OTG_D_P_7") (pintype "passive+no_connect"))
    )
    (net (code "137") (name "unconnected-(JX1-OTG_ID-Pad5)") (class "Default")
      (node (ref "JX1") (pin "5") (pinfunction "OTG_ID_5") (pintype "passive+no_connect"))
    )
    (net (code "138") (name "unconnected-(JX1-OTG_VBUS-Pad170)") (class "Default")
      (node (ref "JX1") (pin "170") (pinfunction "OTG_VBUS_170") (pintype "passive+no_connect"))
    )
    (net (code "139") (name "unconnected-(JX1-OTG_VBUS-Pad171)") (class "Default")
      (node (ref "JX1") (pin "171") (pinfunction "OTG_VBUS_171") (pintype "passive+no_connect"))
    )
    (net (code "140") (name "unconnected-(P10-Pad1)") (class "Default")
      (node (ref "P10") (pin "1") (pinfunction "1_1") (pintype "passive+no_connect"))
    )
    (net (code "141") (name "unconnected-(P10-Pad4)") (class "Default")
      (node (ref "P10") (pin "4") (pinfunction "4_4") (pintype "passive+no_connect"))
    )
    (net (code "142") (name "unconnected-(P10-Pad5)") (class "Default")
      (node (ref "P10") (pin "5") (pinfunction "5_5") (pintype "passive+no_connect"))
    )
    (net (code "143") (name "unconnected-(P10-Pad8)") (class "Default")
      (node (ref "P10") (pin "8") (pinfunction "8_8") (pintype "passive+no_connect"))
    )
    (net (code "144") (name "unconnected-(P10-Pad9)") (class "Default")
      (node (ref "P10") (pin "9") (pinfunction "9_9") (pintype "passive+no_connect"))
    )
    (net (code "145") (name "unconnected-(U17-NC-Pad5)") (class "Default")
      (node (ref "U17") (pin "5") (pinfunction "NC_5") (pintype "passive+no_connect"))
    )
    (net (code "146") (name "unconnected-(U17-NC-Pad8)") (class "Default")
      (node (ref "U17") (pin "8") (pinfunction "NC_8") (pintype "passive+no_connect"))
    )
  )
)
